# matts_pcb_schematic_v2.net
KiCad netlist of a schematic drawn in EAGLE
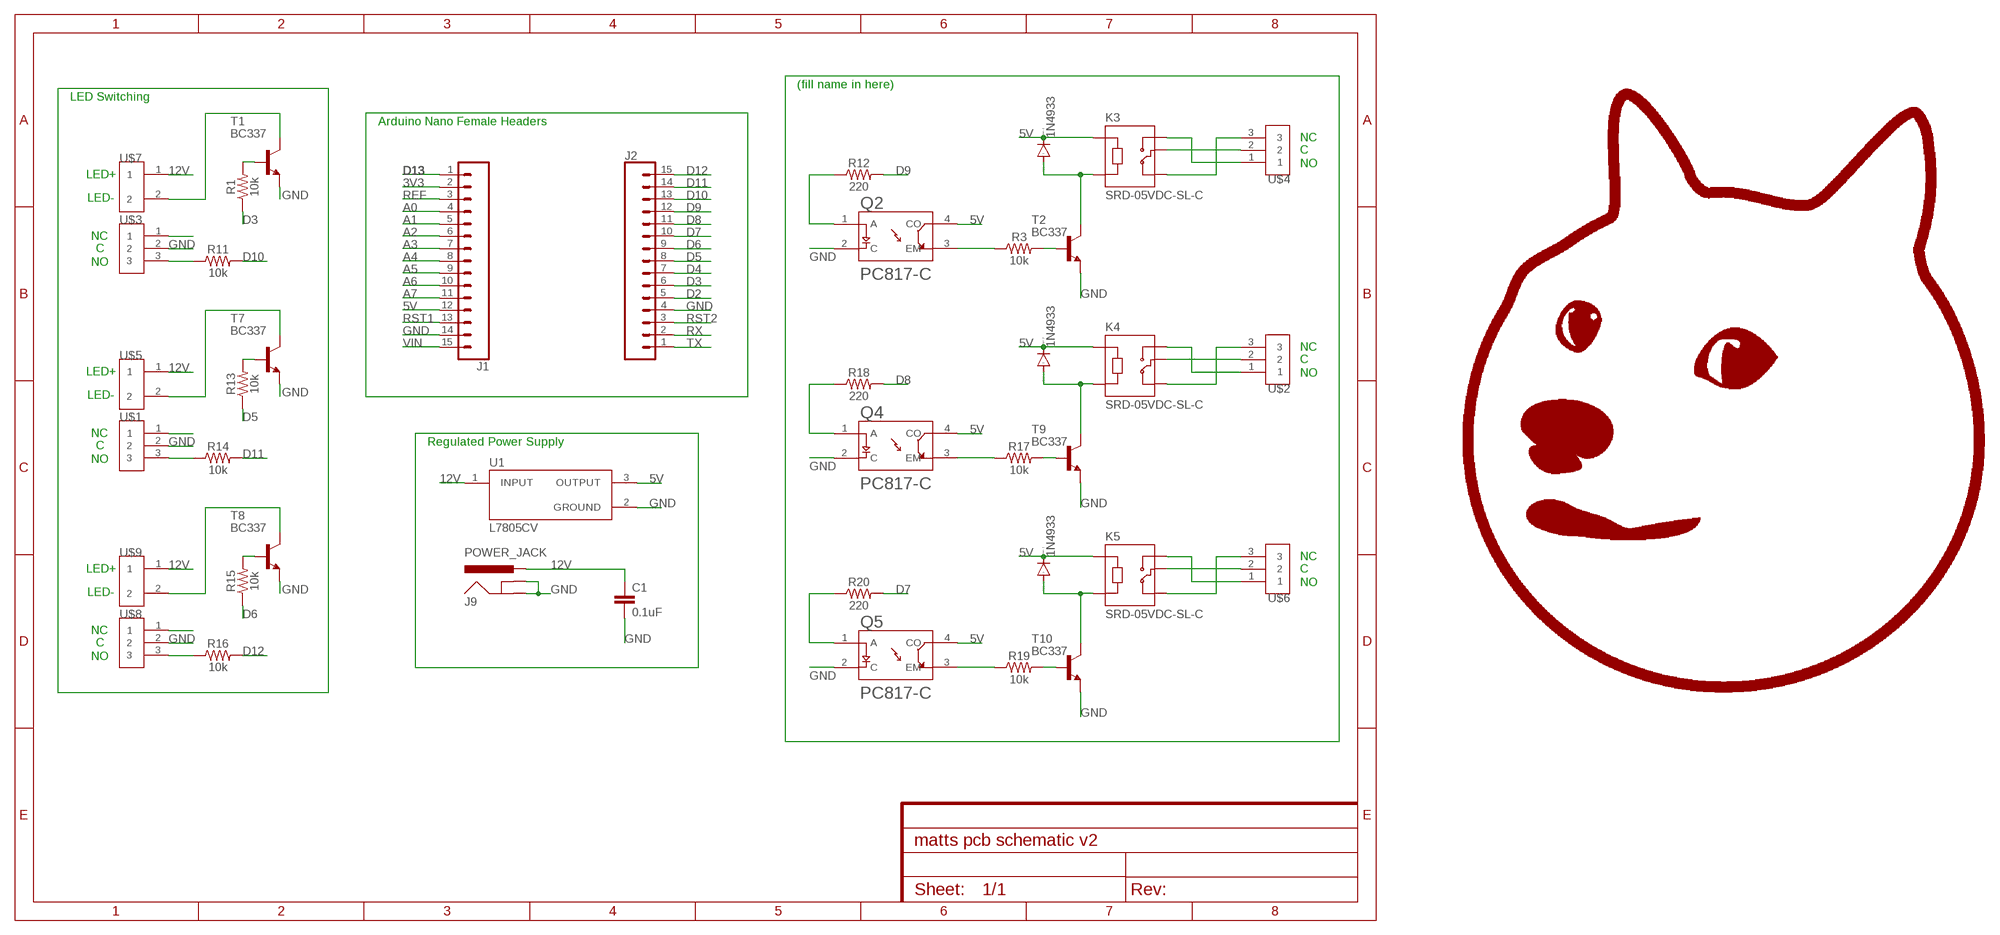
[diagram p0: schematic, sheet 1]

(export (version "E")
  (design (tool "Eeschema 10.0.6"))
  (components
    (comp (ref "C1")
      (value "0.1uF")
      (footprint "eagle-import:CAP-PTH-SMALL-KIT")
      (libsource (lib "eagle-import") (part "0.1UF-KIT-EZ-50V-20%"))
    )
    (comp (ref "D1")
      (value "1N4933")
      (footprint "eagle-import:DO41-10")
      (libsource (lib "eagle-import") (part "1N4933"))
    )
    (comp (ref "D4")
      (value "1N4933")
      (footprint "eagle-import:DO41-10")
      (libsource (lib "eagle-import") (part "1N4933"))
    )
    (comp (ref "D5")
      (value "1N4933")
      (footprint "eagle-import:DO41-10")
      (libsource (lib "eagle-import") (part "1N4933"))
    )
    (comp (ref "J1")
      (value "CONN_15")
      (footprint "eagle-import:1X15")
      (libsource (lib "eagle-import") (part "CONN_15"))
    )
    (comp (ref "J2")
      (value "CONN_15")
      (footprint "eagle-import:1X15")
      (libsource (lib "eagle-import") (part "CONN_15"))
    )
    (comp (ref "J9")
      (value "POWER_JACK")
      (footprint "eagle-import:POWER_JACK_PTH")
      (libsource (lib "eagle-import") (part "POWER_JACK"))
    )
    (comp (ref "K3")
      (value "SRD-05VDC-SL-C")
      (footprint "eagle-import:RELAY_SRD-05VDC-SL-C")
      (fields (field (name "MF") "Songle Relay"))
      (libsource (lib "eagle-import") (part "SRD-05VDC-SL-C"))
    )
    (comp (ref "K4")
      (value "SRD-05VDC-SL-C")
      (footprint "eagle-import:RELAY_SRD-05VDC-SL-C")
      (fields (field (name "MF") "Songle Relay"))
      (libsource (lib "eagle-import") (part "SRD-05VDC-SL-C"))
    )
    (comp (ref "K5")
      (value "SRD-05VDC-SL-C")
      (footprint "eagle-import:RELAY_SRD-05VDC-SL-C")
      (fields (field (name "MF") "Songle Relay"))
      (libsource (lib "eagle-import") (part "SRD-05VDC-SL-C"))
    )
    (comp (ref "Q2")
      (value "PC817-C")
      (footprint "eagle-import:DIP762W50P254L508H350Q4")
      (fields (field (name "MF") "Taiwan Semiconductor"))
      (libsource (lib "eagle-import") (part "PC817-C"))
    )
    (comp (ref "Q4")
      (value "PC817-C")
      (footprint "eagle-import:DIP762W50P254L508H350Q4")
      (fields (field (name "MF") "Taiwan Semiconductor"))
      (libsource (lib "eagle-import") (part "PC817-C"))
    )
    (comp (ref "Q5")
      (value "PC817-C")
      (footprint "eagle-import:DIP762W50P254L508H350Q4")
      (fields (field (name "MF") "Taiwan Semiconductor"))
      (libsource (lib "eagle-import") (part "PC817-C"))
    )
    (comp (ref "R1")
      (value "10k")
      (footprint "eagle-import:AXIAL-0.3")
      (libsource (lib "eagle-import") (part "100KOHM-HORIZ-1/4W-1%"))
    )
    (comp (ref "R3")
      (value "10k")
      (footprint "eagle-import:AXIAL-0.3")
      (libsource (lib "eagle-import") (part "100KOHM-HORIZ-1/4W-1%"))
    )
    (comp (ref "R11")
      (value "10k")
      (footprint "eagle-import:AXIAL-0.3")
      (libsource (lib "eagle-import") (part "100KOHM-HORIZ-1/4W-1%"))
    )
    (comp (ref "R12")
      (value "220")
      (footprint "eagle-import:AXIAL-0.3")
      (libsource (lib "eagle-import") (part "100KOHM-HORIZ-1/4W-1%"))
    )
    (comp (ref "R13")
      (value "10k")
      (footprint "eagle-import:AXIAL-0.3")
      (libsource (lib "eagle-import") (part "100KOHM-HORIZ-1/4W-1%"))
    )
    (comp (ref "R14")
      (value "10k")
      (footprint "eagle-import:AXIAL-0.3")
      (libsource (lib "eagle-import") (part "100KOHM-HORIZ-1/4W-1%"))
    )
    (comp (ref "R15")
      (value "10k")
      (footprint "eagle-import:AXIAL-0.3")
      (libsource (lib "eagle-import") (part "100KOHM-HORIZ-1/4W-1%"))
    )
    (comp (ref "R16")
      (value "10k")
      (footprint "eagle-import:AXIAL-0.3")
      (libsource (lib "eagle-import") (part "100KOHM-HORIZ-1/4W-1%"))
    )
    (comp (ref "R17")
      (value "10k")
      (footprint "eagle-import:AXIAL-0.3")
      (libsource (lib "eagle-import") (part "100KOHM-HORIZ-1/4W-1%"))
    )
    (comp (ref "R18")
      (value "220")
      (footprint "eagle-import:AXIAL-0.3")
      (libsource (lib "eagle-import") (part "100KOHM-HORIZ-1/4W-1%"))
    )
    (comp (ref "R19")
      (value "10k")
      (footprint "eagle-import:AXIAL-0.3")
      (libsource (lib "eagle-import") (part "100KOHM-HORIZ-1/4W-1%"))
    )
    (comp (ref "R20")
      (value "220")
      (footprint "eagle-import:AXIAL-0.3")
      (libsource (lib "eagle-import") (part "100KOHM-HORIZ-1/4W-1%"))
    )
    (comp (ref "T1")
      (value "BC337")
      (footprint "eagle-import:TO92")
      (libsource (lib "eagle-import") (part "BC337"))
    )
    (comp (ref "T2")
      (value "BC337")
      (footprint "eagle-import:TO92")
      (libsource (lib "eagle-import") (part "BC337"))
    )
    (comp (ref "T7")
      (value "BC337")
      (footprint "eagle-import:TO92")
      (libsource (lib "eagle-import") (part "BC337"))
    )
    (comp (ref "T8")
      (value "BC337")
      (footprint "eagle-import:TO92")
      (libsource (lib "eagle-import") (part "BC337"))
    )
    (comp (ref "T9")
      (value "BC337")
      (footprint "eagle-import:TO92")
      (libsource (lib "eagle-import") (part "BC337"))
    )
    (comp (ref "T10")
      (value "BC337")
      (footprint "eagle-import:TO92")
      (libsource (lib "eagle-import") (part "BC337"))
    )
    (comp (ref "U$1")
      (value "3PIN_0.2PITCH_SCREW_TERMINAL")
      (footprint "eagle-import:3PIN_0.2PITCH_SCREW_TERMINAL")
      (libsource (lib "eagle-import") (part "3PIN_0.2PITCH_SCREW_TERMINAL"))
    )
    (comp (ref "U$2")
      (value "3PIN_0.2PITCH_SCREW_TERMINAL")
      (footprint "eagle-import:3PIN_0.2PITCH_SCREW_TERMINAL")
      (libsource (lib "eagle-import") (part "3PIN_0.2PITCH_SCREW_TERMINAL"))
    )
    (comp (ref "U$3")
      (value "3PIN_0.2PITCH_SCREW_TERMINAL")
      (footprint "eagle-import:3PIN_0.2PITCH_SCREW_TERMINAL")
      (libsource (lib "eagle-import") (part "3PIN_0.2PITCH_SCREW_TERMINAL"))
    )
    (comp (ref "U$4")
      (value "3PIN_0.2PITCH_SCREW_TERMINAL")
      (footprint "eagle-import:3PIN_0.2PITCH_SCREW_TERMINAL")
      (libsource (lib "eagle-import") (part "3PIN_0.2PITCH_SCREW_TERMINAL"))
    )
    (comp (ref "U$5")
      (value "2PIN_0.2PITCH_SCREW_TERMINAL")
      (footprint "eagle-import:2PIN_0.2PITCH_SCREW_TERMINAL")
      (libsource (lib "eagle-import") (part "2PIN_0.2PITCH_SCREW_TERMINAL"))
    )
    (comp (ref "U$6")
      (value "3PIN_0.2PITCH_SCREW_TERMINAL")
      (footprint "eagle-import:3PIN_0.2PITCH_SCREW_TERMINAL")
      (libsource (lib "eagle-import") (part "3PIN_0.2PITCH_SCREW_TERMINAL"))
    )
    (comp (ref "U$7")
      (value "2PIN_0.2PITCH_SCREW_TERMINAL")
      (footprint "eagle-import:2PIN_0.2PITCH_SCREW_TERMINAL")
      (libsource (lib "eagle-import") (part "2PIN_0.2PITCH_SCREW_TERMINAL"))
    )
    (comp (ref "U$8")
      (value "3PIN_0.2PITCH_SCREW_TERMINAL")
      (footprint "eagle-import:3PIN_0.2PITCH_SCREW_TERMINAL")
      (libsource (lib "eagle-import") (part "3PIN_0.2PITCH_SCREW_TERMINAL"))
    )
    (comp (ref "U$9")
      (value "2PIN_0.2PITCH_SCREW_TERMINAL")
      (footprint "eagle-import:2PIN_0.2PITCH_SCREW_TERMINAL")
      (libsource (lib "eagle-import") (part "2PIN_0.2PITCH_SCREW_TERMINAL"))
    )
    (comp (ref "U$10")
      (value "DANK_DOGE")
      (footprint "eagle-import:DANK_DOGE")
      (libsource (lib "eagle-import") (part "DANK_DOGE"))
    )
    (comp (ref "U1")
      (value "L7805CV")
      (footprint "eagle-import:TO255P1040X460X1968-3")
      (fields (field (name "MF") "STMicroelectronics"))
      (libsource (lib "eagle-import") (part "L7805CV"))
    )
  )
  (nets
    (net (code "1") (name "/3V3") (class "Default")
      (node (ref "J1") (pin "2") (pinfunction "2_2") (pintype "passive"))
    )
    (net (code "2") (name "/5V") (class "Default")
      (node (ref "D1") (pin "C") (pinfunction "C_C") (pintype "passive"))
      (node (ref "D4") (pin "C") (pinfunction "C_C") (pintype "passive"))
      (node (ref "D5") (pin "C") (pinfunction "C_C") (pintype "passive"))
      (node (ref "J1") (pin "12") (pinfunction "12_12") (pintype "passive"))
      (node (ref "K3") (pin "A1") (pinfunction "A1_A1") (pintype "passive"))
      (node (ref "K4") (pin "A1") (pinfunction "A1_A1") (pintype "passive"))
      (node (ref "K5") (pin "A1") (pinfunction "A1_A1") (pintype "passive"))
      (node (ref "Q2") (pin "4") (pinfunction "CO_4") (pintype "passive"))
      (node (ref "Q4") (pin "4") (pinfunction "CO_4") (pintype "passive"))
      (node (ref "Q5") (pin "4") (pinfunction "CO_4") (pintype "passive"))
      (node (ref "U1") (pin "3") (pinfunction "OUTPUT_3") (pintype "output"))
    )
    (net (code "3") (name "/12V") (class "Default")
      (node (ref "C1") (pin "1") (pinfunction "1_1") (pintype "passive"))
      (node (ref "J9") (pin "PWR") (pinfunction "PWR_PWR") (pintype "bidirectional"))
      (node (ref "U$5") (pin "1") (pinfunction "1_1") (pintype "bidirectional"))
      (node (ref "U$7") (pin "1") (pinfunction "1_1") (pintype "bidirectional"))
      (node (ref "U$9") (pin "1") (pinfunction "1_1") (pintype "bidirectional"))
      (node (ref "U1") (pin "1") (pinfunction "INPUT_1") (pintype "input"))
    )
    (net (code "4") (name "/A0") (class "Default")
      (node (ref "J1") (pin "4") (pinfunction "4_4") (pintype "passive"))
    )
    (net (code "5") (name "/A1") (class "Default")
      (node (ref "J1") (pin "5") (pinfunction "5_5") (pintype "passive"))
    )
    (net (code "6") (name "/A2") (class "Default")
      (node (ref "J1") (pin "6") (pinfunction "6_6") (pintype "passive"))
    )
    (net (code "7") (name "/A3") (class "Default")
      (node (ref "J1") (pin "7") (pinfunction "7_7") (pintype "passive"))
    )
    (net (code "8") (name "/A4") (class "Default")
      (node (ref "J1") (pin "8") (pinfunction "8_8") (pintype "passive"))
    )
    (net (code "9") (name "/A5") (class "Default")
      (node (ref "J1") (pin "9") (pinfunction "9_9") (pintype "passive"))
    )
    (net (code "10") (name "/A6") (class "Default")
      (node (ref "J1") (pin "10") (pinfunction "10_10") (pintype "passive"))
    )
    (net (code "11") (name "/A7") (class "Default")
      (node (ref "J1") (pin "11") (pinfunction "11_11") (pintype "passive"))
    )
    (net (code "12") (name "/D2") (class "Default")
      (node (ref "J2") (pin "5") (pinfunction "5_5") (pintype "passive"))
    )
    (net (code "13") (name "/D3") (class "Default")
      (node (ref "J2") (pin "6") (pinfunction "6_6") (pintype "passive"))
      (node (ref "R1") (pin "P$1") (pinfunction "1_P$1") (pintype "passive"))
    )
    (net (code "14") (name "/D4") (class "Default")
      (node (ref "J2") (pin "7") (pinfunction "7_7") (pintype "passive"))
    )
    (net (code "15") (name "/D5") (class "Default")
      (node (ref "J2") (pin "8") (pinfunction "8_8") (pintype "passive"))
      (node (ref "R13") (pin "P$1") (pinfunction "1_P$1") (pintype "passive"))
    )
    (net (code "16") (name "/D6") (class "Default")
      (node (ref "J2") (pin "9") (pinfunction "9_9") (pintype "passive"))
      (node (ref "R15") (pin "P$1") (pinfunction "1_P$1") (pintype "passive"))
    )
    (net (code "17") (name "/D7") (class "Default")
      (node (ref "J2") (pin "10") (pinfunction "10_10") (pintype "passive"))
      (node (ref "R20") (pin "P$2") (pinfunction "2_P$2") (pintype "passive"))
    )
    (net (code "18") (name "/D8") (class "Default")
      (node (ref "J2") (pin "11") (pinfunction "11_11") (pintype "passive"))
      (node (ref "R18") (pin "P$2") (pinfunction "2_P$2") (pintype "passive"))
    )
    (net (code "19") (name "/D9") (class "Default")
      (node (ref "J2") (pin "12") (pinfunction "12_12") (pintype "passive"))
      (node (ref "R12") (pin "P$2") (pinfunction "2_P$2") (pintype "passive"))
    )
    (net (code "20") (name "/D10") (class "Default")
      (node (ref "J2") (pin "13") (pinfunction "13_13") (pintype "passive"))
      (node (ref "R11") (pin "P$2") (pinfunction "2_P$2") (pintype "passive"))
    )
    (net (code "21") (name "/D11") (class "Default")
      (node (ref "J2") (pin "14") (pinfunction "14_14") (pintype "passive"))
      (node (ref "R14") (pin "P$2") (pinfunction "2_P$2") (pintype "passive"))
    )
    (net (code "22") (name "/D12") (class "Default")
      (node (ref "J2") (pin "15") (pinfunction "15_15") (pintype "passive"))
      (node (ref "R16") (pin "P$2") (pinfunction "2_P$2") (pintype "passive"))
    )
    (net (code "23") (name "/D13") (class "Default")
      (node (ref "J1") (pin "1") (pinfunction "1_1") (pintype "passive"))
    )
    (net (code "24") (name "/GND") (class "Default")
      (node (ref "C1") (pin "2") (pinfunction "2_2") (pintype "passive"))
      (node (ref "J1") (pin "14") (pinfunction "14_14") (pintype "passive"))
      (node (ref "J2") (pin "4") (pinfunction "4_4") (pintype "passive"))
      (node (ref "J9") (pin "GND") (pinfunction "GND_GND") (pintype "bidirectional"))
      (node (ref "J9") (pin "GNDBREAK") (pinfunction "GNDBREAK_GNDBREAK") (pintype "bidirectional"))
      (node (ref "Q2") (pin "2") (pinfunction "C_2") (pintype "passive"))
      (node (ref "Q4") (pin "2") (pinfunction "C_2") (pintype "passive"))
      (node (ref "Q5") (pin "2") (pinfunction "C_2") (pintype "passive"))
      (node (ref "T1") (pin "1") (pinfunction "E_1") (pintype "passive"))
      (node (ref "T10") (pin "1") (pinfunction "E_1") (pintype "passive"))
      (node (ref "T2") (pin "1") (pinfunction "E_1") (pintype "passive"))
      (node (ref "T7") (pin "1") (pinfunction "E_1") (pintype "passive"))
      (node (ref "T8") (pin "1") (pinfunction "E_1") (pintype "passive"))
      (node (ref "T9") (pin "1") (pinfunction "E_1") (pintype "passive"))
      (node (ref "U$1") (pin "2") (pinfunction "2_2") (pintype "bidirectional"))
      (node (ref "U$3") (pin "2") (pinfunction "2_2") (pintype "bidirectional"))
      (node (ref "U$8") (pin "2") (pinfunction "2_2") (pintype "bidirectional"))
      (node (ref "U1") (pin "2") (pinfunction "GROUND_2") (pintype "power_in"))
    )
    (net (code "25") (name "/REF") (class "Default")
      (node (ref "J1") (pin "3") (pinfunction "3_3") (pintype "passive"))
    )
    (net (code "26") (name "/RST1") (class "Default")
      (node (ref "J1") (pin "13") (pinfunction "13_13") (pintype "passive"))
    )
    (net (code "27") (name "/RST2") (class "Default")
      (node (ref "J2") (pin "3") (pinfunction "3_3") (pintype "passive"))
    )
    (net (code "28") (name "/RX") (class "Default")
      (node (ref "J2") (pin "2") (pinfunction "2_2") (pintype "passive"))
    )
    (net (code "29") (name "/TX") (class "Default")
      (node (ref "J2") (pin "1") (pinfunction "1_1") (pintype "passive"))
    )
    (net (code "30") (name "/VIN") (class "Default")
      (node (ref "J1") (pin "15") (pinfunction "15_15") (pintype "passive"))
    )
    (net (code "31") (name "Net-(K3-PadCOM)") (class "Default")
      (node (ref "K3") (pin "COM") (pinfunction "COM_COM") (pintype "passive"))
      (node (ref "U$4") (pin "2") (pinfunction "2_2") (pintype "bidirectional"))
    )
    (net (code "32") (name "Net-(K3-PadNC)") (class "Default")
      (node (ref "K3") (pin "NC") (pinfunction "NC_NC") (pintype "passive"))
      (node (ref "U$4") (pin "3") (pinfunction "3_3") (pintype "bidirectional"))
    )
    (net (code "33") (name "Net-(K3-PadNO)") (class "Default")
      (node (ref "K3") (pin "NO") (pinfunction "NO_NO") (pintype "passive"))
      (node (ref "U$4") (pin "1") (pinfunction "1_1") (pintype "bidirectional"))
    )
    (net (code "34") (name "Net-(K4-PadCOM)") (class "Default")
      (node (ref "K4") (pin "COM") (pinfunction "COM_COM") (pintype "passive"))
      (node (ref "U$2") (pin "2") (pinfunction "2_2") (pintype "bidirectional"))
    )
    (net (code "35") (name "Net-(K4-PadNC)") (class "Default")
      (node (ref "K4") (pin "NC") (pinfunction "NC_NC") (pintype "passive"))
      (node (ref "U$2") (pin "3") (pinfunction "3_3") (pintype "bidirectional"))
    )
    (net (code "36") (name "Net-(K4-PadNO)") (class "Default")
      (node (ref "K4") (pin "NO") (pinfunction "NO_NO") (pintype "passive"))
      (node (ref "U$2") (pin "1") (pinfunction "1_1") (pintype "bidirectional"))
    )
    (net (code "37") (name "Net-(K5-PadCOM)") (class "Default")
      (node (ref "K5") (pin "COM") (pinfunction "COM_COM") (pintype "passive"))
      (node (ref "U$6") (pin "2") (pinfunction "2_2") (pintype "bidirectional"))
    )
    (net (code "38") (name "Net-(K5-PadNC)") (class "Default")
      (node (ref "K5") (pin "NC") (pinfunction "NC_NC") (pintype "passive"))
      (node (ref "U$6") (pin "3") (pinfunction "3_3") (pintype "bidirectional"))
    )
    (net (code "39") (name "Net-(K5-PadNO)") (class "Default")
      (node (ref "K5") (pin "NO") (pinfunction "NO_NO") (pintype "passive"))
      (node (ref "U$6") (pin "1") (pinfunction "1_1") (pintype "bidirectional"))
    )
    (net (code "40") (name "Net-(Q2-A)") (class "Default")
      (node (ref "Q2") (pin "1") (pinfunction "A_1") (pintype "passive"))
      (node (ref "R12") (pin "P$1") (pinfunction "1_P$1") (pintype "passive"))
    )
    (net (code "41") (name "Net-(Q2-EM)") (class "Default")
      (node (ref "Q2") (pin "3") (pinfunction "EM_3") (pintype "passive"))
      (node (ref "R3") (pin "P$1") (pinfunction "1_P$1") (pintype "passive"))
    )
    (net (code "42") (name "Net-(Q4-A)") (class "Default")
      (node (ref "Q4") (pin "1") (pinfunction "A_1") (pintype "passive"))
      (node (ref "R18") (pin "P$1") (pinfunction "1_P$1") (pintype "passive"))
    )
    (net (code "43") (name "Net-(Q4-EM)") (class "Default")
      (node (ref "Q4") (pin "3") (pinfunction "EM_3") (pintype "passive"))
      (node (ref "R17") (pin "P$1") (pinfunction "1_P$1") (pintype "passive"))
    )
    (net (code "44") (name "Net-(Q5-A)") (class "Default")
      (node (ref "Q5") (pin "1") (pinfunction "A_1") (pintype "passive"))
      (node (ref "R20") (pin "P$1") (pinfunction "1_P$1") (pintype "passive"))
    )
    (net (code "45") (name "Net-(Q5-EM)") (class "Default")
      (node (ref "Q5") (pin "3") (pinfunction "EM_3") (pintype "passive"))
      (node (ref "R19") (pin "P$1") (pinfunction "1_P$1") (pintype "passive"))
    )
    (net (code "46") (name "Net-(R1-2)") (class "Default")
      (node (ref "R1") (pin "P$2") (pinfunction "2_P$2") (pintype "passive"))
      (node (ref "T1") (pin "2") (pinfunction "B_2") (pintype "passive"))
    )
    (net (code "47") (name "Net-(R3-2)") (class "Default")
      (node (ref "R3") (pin "P$2") (pinfunction "2_P$2") (pintype "passive"))
      (node (ref "T2") (pin "2") (pinfunction "B_2") (pintype "passive"))
    )
    (net (code "48") (name "Net-(R11-1)") (class "Default")
      (node (ref "R11") (pin "P$1") (pinfunction "1_P$1") (pintype "passive"))
      (node (ref "U$3") (pin "3") (pinfunction "3_3") (pintype "bidirectional"))
    )
    (net (code "49") (name "Net-(R13-2)") (class "Default")
      (node (ref "R13") (pin "P$2") (pinfunction "2_P$2") (pintype "passive"))
      (node (ref "T7") (pin "2") (pinfunction "B_2") (pintype "passive"))
    )
    (net (code "50") (name "Net-(R14-1)") (class "Default")
      (node (ref "R14") (pin "P$1") (pinfunction "1_P$1") (pintype "passive"))
      (node (ref "U$1") (pin "3") (pinfunction "3_3") (pintype "bidirectional"))
    )
    (net (code "51") (name "Net-(R15-2)") (class "Default")
      (node (ref "R15") (pin "P$2") (pinfunction "2_P$2") (pintype "passive"))
      (node (ref "T8") (pin "2") (pinfunction "B_2") (pintype "passive"))
    )
    (net (code "52") (name "Net-(R16-1)") (class "Default")
      (node (ref "R16") (pin "P$1") (pinfunction "1_P$1") (pintype "passive"))
      (node (ref "U$8") (pin "3") (pinfunction "3_3") (pintype "bidirectional"))
    )
    (net (code "53") (name "Net-(R17-2)") (class "Default")
      (node (ref "R17") (pin "P$2") (pinfunction "2_P$2") (pintype "passive"))
      (node (ref "T9") (pin "2") (pinfunction "B_2") (pintype "passive"))
    )
    (net (code "54") (name "Net-(R19-2)") (class "Default")
      (node (ref "R19") (pin "P$2") (pinfunction "2_P$2") (pintype "passive"))
      (node (ref "T10") (pin "2") (pinfunction "B_2") (pintype "passive"))
    )
    (net (code "55") (name "Net-(T1-C)") (class "Default")
      (node (ref "T1") (pin "3") (pinfunction "C_3") (pintype "passive"))
      (node (ref "U$7") (pin "2") (pinfunction "2_2") (pintype "bidirectional"))
    )
    (net (code "56") (name "Net-(T2-C)") (class "Default")
      (node (ref "D1") (pin "A") (pinfunction "A_A") (pintype "passive"))
      (node (ref "K3") (pin "A2") (pinfunction "A2_A2") (pintype "passive"))
      (node (ref "T2") (pin "3") (pinfunction "C_3") (pintype "passive"))
    )
    (net (code "57") (name "Net-(T7-C)") (class "Default")
      (node (ref "T7") (pin "3") (pinfunction "C_3") (pintype "passive"))
      (node (ref "U$5") (pin "2") (pinfunction "2_2") (pintype "bidirectional"))
    )
    (net (code "58") (name "Net-(T8-C)") (class "Default")
      (node (ref "T8") (pin "3") (pinfunction "C_3") (pintype "passive"))
      (node (ref "U$9") (pin "2") (pinfunction "2_2") (pintype "bidirectional"))
    )
    (net (code "59") (name "Net-(T9-C)") (class "Default")
      (node (ref "D4") (pin "A") (pinfunction "A_A") (pintype "passive"))
      (node (ref "K4") (pin "A2") (pinfunction "A2_A2") (pintype "passive"))
      (node (ref "T9") (pin "3") (pinfunction "C_3") (pintype "passive"))
    )
    (net (code "60") (name "Net-(T10-C)") (class "Default")
      (node (ref "D5") (pin "A") (pinfunction "A_A") (pintype "passive"))
      (node (ref "K5") (pin "A2") (pinfunction "A2_A2") (pintype "passive"))
      (node (ref "T10") (pin "3") (pinfunction "C_3") (pintype "passive"))
    )
    (net (code "61") (name "unconnected-(U$1-Pad1)") (class "Default")
      (node (ref "U$1") (pin "1") (pinfunction "1_1") (pintype "bidirectional"))
    )
    (net (code "62") (name "unconnected-(U$3-Pad1)") (class "Default")
      (node (ref "U$3") (pin "1") (pinfunction "1_1") (pintype "bidirectional"))
    )
    (net (code "63") (name "unconnected-(U$8-Pad1)") (class "Default")
      (node (ref "U$8") (pin "1") (pinfunction "1_1") (pintype "bidirectional"))
    )
  )
)
